# BMP384_Breakout.net
KiCad netlist of a schematic drawn in EAGLE
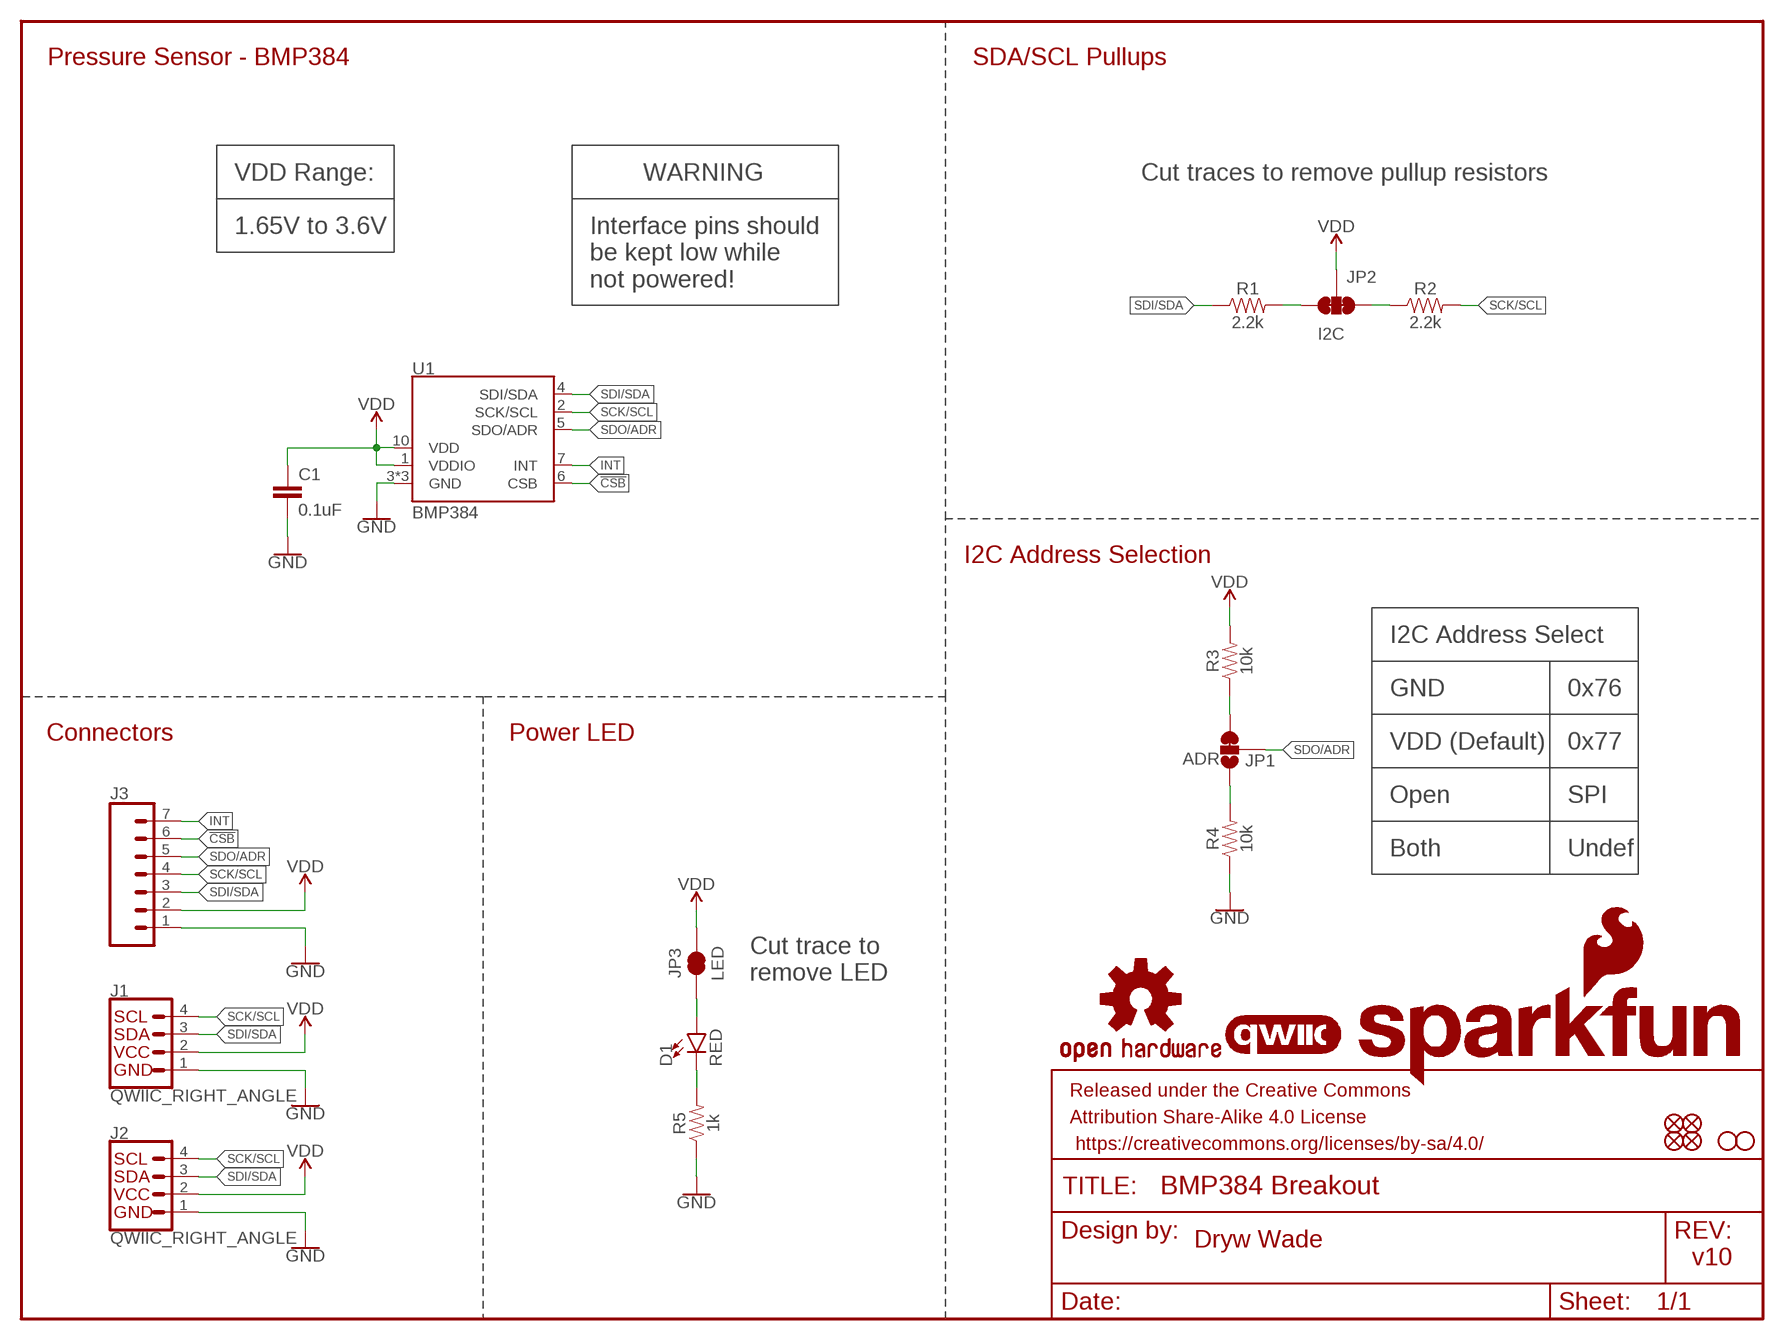
[diagram p0: schematic, sheet 1]

(export (version "E")
  (design (tool "Eeschema 10.0.6"))
  (components
    (comp (ref "C1")
      (value "0.1uF")
      (footprint "eagle-import:0603")
      (libsource (lib "eagle-import") (part "0.1UF-0603-25V-(+80/-20%)"))
    )
    (comp (ref "D1")
      (value "RED")
      (footprint "eagle-import:LED-0603")
      (libsource (lib "eagle-import") (part "LED-RED0603"))
    )
    (comp (ref "FD1")
      (value "FIDUCIAL1X2")
      (footprint "eagle-import:FIDUCIAL-1X2")
      (libsource (lib "eagle-import") (part "FIDUCIAL1X2"))
    )
    (comp (ref "FD2")
      (value "FIDUCIAL1X2")
      (footprint "eagle-import:FIDUCIAL-1X2")
      (libsource (lib "eagle-import") (part "FIDUCIAL1X2"))
    )
    (comp (ref "FD3")
      (value "FIDUCIAL1X2")
      (footprint "eagle-import:FIDUCIAL-1X2")
      (libsource (lib "eagle-import") (part "FIDUCIAL1X2"))
    )
    (comp (ref "FD4")
      (value "FIDUCIAL1X2")
      (footprint "eagle-import:FIDUCIAL-1X2")
      (libsource (lib "eagle-import") (part "FIDUCIAL1X2"))
    )
    (comp (ref "FRAME1")
      (value "FRAME-LETTER")
      (footprint "eagle-import:CREATIVE_COMMONS")
      (libsource (lib "eagle-import") (part "FRAME-LETTER"))
    )
    (comp (ref "H1")
      (value "STAND-OFF")
      (footprint "eagle-import:STAND-OFF")
      (libsource (lib "eagle-import") (part "STAND-OFF"))
    )
    (comp (ref "H2")
      (value "STAND-OFF")
      (footprint "eagle-import:STAND-OFF")
      (libsource (lib "eagle-import") (part "STAND-OFF"))
    )
    (comp (ref "J1")
      (value "QWIIC_RIGHT_ANGLE")
      (footprint "eagle-import:JST04_1MM_RA")
      (libsource (lib "eagle-import") (part "QWIIC_CONNECTORJS-1MM"))
    )
    (comp (ref "J2")
      (value "QWIIC_RIGHT_ANGLE")
      (footprint "eagle-import:JST04_1MM_RA")
      (libsource (lib "eagle-import") (part "QWIIC_CONNECTORJS-1MM"))
    )
    (comp (ref "J3")
      (value "CONN_07NO_SILK")
      (footprint "eagle-import:1X07_NO_SILK")
      (libsource (lib "eagle-import") (part "CONN_07NO_SILK"))
    )
    (comp (ref "JP1")
      (value "ADR")
      (footprint "eagle-import:SMT-JUMPER_3_1-NC_TRACE_SILK")
      (libsource (lib "eagle-import") (part "JUMPER-SMT_3_1-NC_TRACE_SILK"))
    )
    (comp (ref "JP2")
      (value "I2C")
      (footprint "eagle-import:SMT-JUMPER_3_2-NC_TRACE_SILK")
      (libsource (lib "eagle-import") (part "JUMPER-SMT_3_2-NC_TRACE_SILK"))
    )
    (comp (ref "JP3")
      (value "LED")
      (footprint "eagle-import:SMT-JUMPER_2_NC_TRACE_SILK")
      (libsource (lib "eagle-import") (part "JUMPER-SMT_2_NC_TRACE_SILK"))
    )
    (comp (ref "LOGO1")
      (value "OSHW-LOGOS")
      (footprint "eagle-import:OSHW-LOGO-S")
      (libsource (lib "eagle-import") (part "OSHW-LOGOS"))
    )
    (comp (ref "LOGO2")
      (value "SFE_LOGO_FLAME.2_INCH")
      (footprint "eagle-import:SFE_LOGO_FLAME_.2")
      (libsource (lib "eagle-import") (part "SFE_LOGO_FLAME.2_INCH"))
    )
    (comp (ref "LOGO3")
      (value "QWIIC_LOGO_5MM")
      (footprint "eagle-import:QWIIC_5MM")
      (libsource (lib "eagle-import") (part "QWIIC_LOGO_5MM"))
    )
    (comp (ref "LOGO4")
      (value "SFE_LOGO_NAME_FLAME.1_INCH")
      (footprint "eagle-import:SFE_LOGO_NAME_FLAME_.1")
      (libsource (lib "eagle-import") (part "SFE_LOGO_NAME_FLAME.1_INCH"))
    )
    (comp (ref "R1")
      (value "2.2k")
      (footprint "eagle-import:0603")
      (libsource (lib "eagle-import") (part "2.2KOHM-0603-1/10W-1%"))
    )
    (comp (ref "R2")
      (value "2.2k")
      (footprint "eagle-import:0603")
      (libsource (lib "eagle-import") (part "2.2KOHM-0603-1/10W-1%"))
    )
    (comp (ref "R3")
      (value "10k")
      (footprint "eagle-import:0603")
      (libsource (lib "eagle-import") (part "10KOHM-0603-1/10W-1%"))
    )
    (comp (ref "R4")
      (value "10k")
      (footprint "eagle-import:0603")
      (libsource (lib "eagle-import") (part "10KOHM-0603-1/10W-1%"))
    )
    (comp (ref "R5")
      (value "1k")
      (footprint "eagle-import:0603")
      (libsource (lib "eagle-import") (part "1KOHM-0603-1/10W-1%"))
    )
    (comp (ref "U1")
      (value "BMP384")
      (footprint "eagle-import:LGA-10")
      (libsource (lib "eagle-import") (part "BMP384"))
    )
  )
  (nets
    (net (code "1") (name "/~{CSB}") (class "Default")
      (node (ref "J3") (pin "6") (pinfunction "6_6") (pintype "passive"))
      (node (ref "U1") (pin "6") (pinfunction "CSB_6") (pintype "input"))
    )
    (net (code "2") (name "GND") (class "Default")
      (node (ref "C1") (pin "2") (pinfunction "2_2") (pintype "passive"))
      (node (ref "J1") (pin "1") (pinfunction "1_1") (pintype "power_in"))
      (node (ref "J2") (pin "1") (pinfunction "1_1") (pintype "power_in"))
      (node (ref "J3") (pin "1") (pinfunction "1_1") (pintype "passive"))
      (node (ref "R4") (pin "1") (pinfunction "1_1") (pintype "passive"))
      (node (ref "R5") (pin "1") (pinfunction "1_1") (pintype "passive"))
      (node (ref "U1") (pin "3") (pinfunction "GND_3") (pintype "power_in"))
      (node (ref "U1") (pin "8") (pinfunction "GND_8") (pintype "power_in"))
      (node (ref "U1") (pin "9") (pinfunction "GND_9") (pintype "power_in"))
    )
    (net (code "3") (name "INT") (class "Default")
      (node (ref "J3") (pin "7") (pinfunction "7_7") (pintype "passive"))
      (node (ref "U1") (pin "7") (pinfunction "INT_7") (pintype "output"))
    )
    (net (code "4") (name "Net-(D1-PadA)") (class "Default")
      (node (ref "D1") (pin "A") (pinfunction "A_A") (pintype "passive"))
      (node (ref "JP3") (pin "1") (pinfunction "1_1") (pintype "passive"))
    )
    (net (code "5") (name "Net-(D1-PadC)") (class "Default")
      (node (ref "D1") (pin "C") (pinfunction "C_C") (pintype "passive"))
      (node (ref "R5") (pin "2") (pinfunction "2_2") (pintype "passive"))
    )
    (net (code "6") (name "Net-(JP1-Pad1)") (class "Default")
      (node (ref "JP1") (pin "1") (pinfunction "1_1") (pintype "passive"))
      (node (ref "R4") (pin "2") (pinfunction "2_2") (pintype "passive"))
    )
    (net (code "7") (name "Net-(JP1-Pad3)") (class "Default")
      (node (ref "JP1") (pin "3") (pinfunction "3_3") (pintype "passive"))
      (node (ref "R3") (pin "1") (pinfunction "1_1") (pintype "passive"))
    )
    (net (code "8") (name "Net-(JP2-Pad1)") (class "Default")
      (node (ref "JP2") (pin "1") (pinfunction "1_1") (pintype "passive"))
      (node (ref "R2") (pin "1") (pinfunction "1_1") (pintype "passive"))
    )
    (net (code "9") (name "Net-(JP2-Pad3)") (class "Default")
      (node (ref "JP2") (pin "3") (pinfunction "3_3") (pintype "passive"))
      (node (ref "R1") (pin "2") (pinfunction "2_2") (pintype "passive"))
    )
    (net (code "10") (name "SCK{slash}SCL") (class "Default")
      (node (ref "J1") (pin "4") (pinfunction "4_4") (pintype "passive"))
      (node (ref "J2") (pin "4") (pinfunction "4_4") (pintype "passive"))
      (node (ref "J3") (pin "4") (pinfunction "4_4") (pintype "passive"))
      (node (ref "R2") (pin "2") (pinfunction "2_2") (pintype "passive"))
      (node (ref "U1") (pin "2") (pinfunction "SCK/SCL_2") (pintype "bidirectional"))
    )
    (net (code "11") (name "SDI{slash}SDA") (class "Default")
      (node (ref "J1") (pin "3") (pinfunction "3_3") (pintype "passive"))
      (node (ref "J2") (pin "3") (pinfunction "3_3") (pintype "passive"))
      (node (ref "J3") (pin "3") (pinfunction "3_3") (pintype "passive"))
      (node (ref "R1") (pin "1") (pinfunction "1_1") (pintype "passive"))
      (node (ref "U1") (pin "4") (pinfunction "SDI/SDA_4") (pintype "bidirectional"))
    )
    (net (code "12") (name "SDO{slash}ADR") (class "Default")
      (node (ref "J3") (pin "5") (pinfunction "5_5") (pintype "passive"))
      (node (ref "JP1") (pin "2") (pinfunction "2_2") (pintype "passive"))
      (node (ref "U1") (pin "5") (pinfunction "SDO/ADR_5") (pintype "bidirectional"))
    )
    (net (code "13") (name "VDD") (class "Default")
      (node (ref "C1") (pin "1") (pinfunction "1_1") (pintype "passive"))
      (node (ref "J1") (pin "2") (pinfunction "2_2") (pintype "power_in"))
      (node (ref "J2") (pin "2") (pinfunction "2_2") (pintype "power_in"))
      (node (ref "J3") (pin "2") (pinfunction "2_2") (pintype "passive"))
      (node (ref "JP2") (pin "2") (pinfunction "2_2") (pintype "passive"))
      (node (ref "JP3") (pin "2") (pinfunction "2_2") (pintype "passive"))
      (node (ref "R3") (pin "2") (pinfunction "2_2") (pintype "passive"))
      (node (ref "U1") (pin "1") (pinfunction "VDDIO_1") (pintype "power_in"))
      (node (ref "U1") (pin "10") (pinfunction "VDD_10") (pintype "power_in"))
    )
  )
)
